# MainBoard.net
KiCad netlist of a schematic drawn in EAGLE
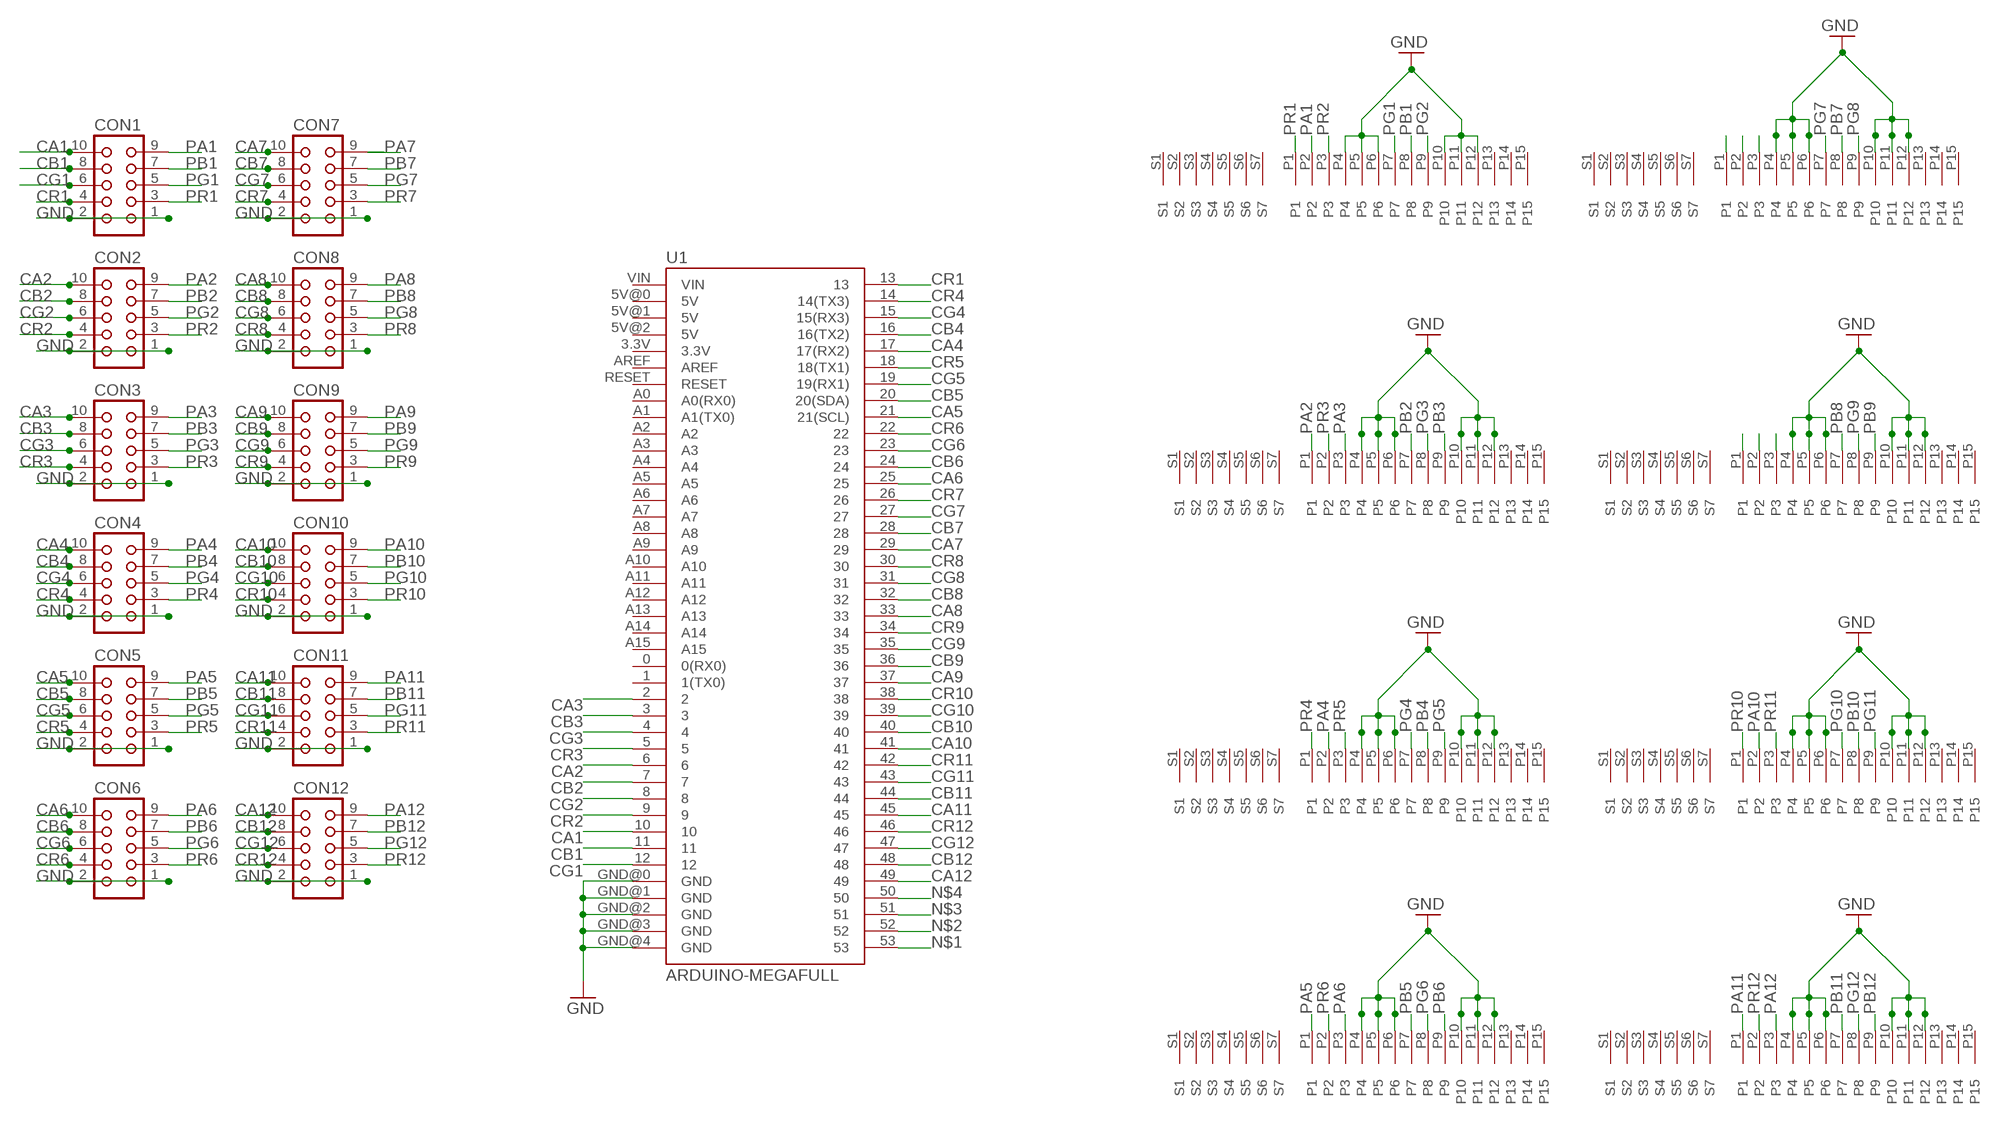
[diagram p0: schematic, sheet 1]

(export (version "E")
  (design (tool "Eeschema 10.0.6"))
  (components
    (comp (ref "CON1")
      (value "CON10")
      (footprint "eagle-import:CON10")
      (libsource (lib "eagle-import") (part "CON10"))
    )
    (comp (ref "CON2")
      (value "CON10")
      (footprint "eagle-import:CON10")
      (libsource (lib "eagle-import") (part "CON10"))
    )
    (comp (ref "CON3")
      (value "CON10")
      (footprint "eagle-import:CON10")
      (libsource (lib "eagle-import") (part "CON10"))
    )
    (comp (ref "CON4")
      (value "CON10")
      (footprint "eagle-import:CON10")
      (libsource (lib "eagle-import") (part "CON10"))
    )
    (comp (ref "CON5")
      (value "CON10")
      (footprint "eagle-import:CON10")
      (libsource (lib "eagle-import") (part "CON10"))
    )
    (comp (ref "CON6")
      (value "CON10")
      (footprint "eagle-import:CON10")
      (libsource (lib "eagle-import") (part "CON10"))
    )
    (comp (ref "CON7")
      (value "CON10")
      (footprint "eagle-import:CON10")
      (libsource (lib "eagle-import") (part "CON10"))
    )
    (comp (ref "CON8")
      (value "CON10")
      (footprint "eagle-import:CON10")
      (libsource (lib "eagle-import") (part "CON10"))
    )
    (comp (ref "CON9")
      (value "CON10")
      (footprint "eagle-import:CON10")
      (libsource (lib "eagle-import") (part "CON10"))
    )
    (comp (ref "CON10")
      (value "CON10")
      (footprint "eagle-import:CON10")
      (libsource (lib "eagle-import") (part "CON10"))
    )
    (comp (ref "CON11")
      (value "CON10")
      (footprint "eagle-import:CON10")
      (libsource (lib "eagle-import") (part "CON10"))
    )
    (comp (ref "CON12")
      (value "CON10")
      (footprint "eagle-import:CON10")
      (libsource (lib "eagle-import") (part "CON10"))
    )
    (comp (ref "P1")
      (value "87779-1001")
      (footprint "eagle-import:87779-1001")
      (libsource (lib "eagle-import") (part "87779-1001"))
    )
    (comp (ref "U$2")
      (value "87779-1001")
      (footprint "eagle-import:87779-1001")
      (libsource (lib "eagle-import") (part "87779-1001"))
    )
    (comp (ref "U$3")
      (value "87779-1001")
      (footprint "eagle-import:87779-1001")
      (libsource (lib "eagle-import") (part "87779-1001"))
    )
    (comp (ref "U$4")
      (value "87779-1001")
      (footprint "eagle-import:87779-1001")
      (libsource (lib "eagle-import") (part "87779-1001"))
    )
    (comp (ref "U$5")
      (value "87779-1001")
      (footprint "eagle-import:87779-1001")
      (libsource (lib "eagle-import") (part "87779-1001"))
    )
    (comp (ref "U$6")
      (value "87779-1001")
      (footprint "eagle-import:87779-1001")
      (libsource (lib "eagle-import") (part "87779-1001"))
    )
    (comp (ref "U$7")
      (value "87779-1001")
      (footprint "eagle-import:87779-1001")
      (libsource (lib "eagle-import") (part "87779-1001"))
    )
    (comp (ref "U$8")
      (value "87779-1001")
      (footprint "eagle-import:87779-1001")
      (libsource (lib "eagle-import") (part "87779-1001"))
    )
    (comp (ref "U1")
      (value "ARDUINO-MEGAFULL")
      (footprint "eagle-import:ARDUINO_MEGA")
      (libsource (lib "eagle-import") (part "ARDUINO-MEGAFULL"))
    )
  )
  (nets
    (net (code "1") (name "/CA1") (class "Default")
      (node (ref "CON1") (pin "10") (pinfunction "10_10") (pintype "passive"))
      (node (ref "U1") (pin "10") (pinfunction "10_10") (pintype "bidirectional"))
    )
    (net (code "2") (name "/CA2") (class "Default")
      (node (ref "CON2") (pin "10") (pinfunction "10_10") (pintype "passive"))
      (node (ref "U1") (pin "6") (pinfunction "6_6") (pintype "bidirectional"))
    )
    (net (code "3") (name "/CA3") (class "Default")
      (node (ref "CON3") (pin "10") (pinfunction "10_10") (pintype "passive"))
      (node (ref "U1") (pin "2") (pinfunction "2_2") (pintype "bidirectional"))
    )
    (net (code "4") (name "/CA4") (class "Default")
      (node (ref "CON4") (pin "10") (pinfunction "10_10") (pintype "passive"))
      (node (ref "U1") (pin "17") (pinfunction "17(RX2)_17") (pintype "bidirectional"))
    )
    (net (code "5") (name "/CA5") (class "Default")
      (node (ref "CON5") (pin "10") (pinfunction "10_10") (pintype "passive"))
      (node (ref "U1") (pin "21") (pinfunction "21(SCL)_21") (pintype "bidirectional"))
    )
    (net (code "6") (name "/CA6") (class "Default")
      (node (ref "CON6") (pin "10") (pinfunction "10_10") (pintype "passive"))
      (node (ref "U1") (pin "25") (pinfunction "25_25") (pintype "bidirectional"))
    )
    (net (code "7") (name "/CA7") (class "Default")
      (node (ref "CON7") (pin "10") (pinfunction "10_10") (pintype "passive"))
      (node (ref "U1") (pin "29") (pinfunction "29_29") (pintype "bidirectional"))
    )
    (net (code "8") (name "/CA8") (class "Default")
      (node (ref "CON8") (pin "10") (pinfunction "10_10") (pintype "passive"))
      (node (ref "U1") (pin "33") (pinfunction "33_33") (pintype "bidirectional"))
    )
    (net (code "9") (name "/CA9") (class "Default")
      (node (ref "CON9") (pin "10") (pinfunction "10_10") (pintype "passive"))
      (node (ref "U1") (pin "37") (pinfunction "37_37") (pintype "bidirectional"))
    )
    (net (code "10") (name "/CA10") (class "Default")
      (node (ref "CON10") (pin "10") (pinfunction "10_10") (pintype "passive"))
      (node (ref "U1") (pin "41") (pinfunction "41_41") (pintype "bidirectional"))
    )
    (net (code "11") (name "/CA11") (class "Default")
      (node (ref "CON11") (pin "10") (pinfunction "10_10") (pintype "passive"))
      (node (ref "U1") (pin "45") (pinfunction "45_45") (pintype "bidirectional"))
    )
    (net (code "12") (name "/CA12") (class "Default")
      (node (ref "CON12") (pin "10") (pinfunction "10_10") (pintype "passive"))
      (node (ref "U1") (pin "49") (pinfunction "49_49") (pintype "bidirectional"))
    )
    (net (code "13") (name "/CB1") (class "Default")
      (node (ref "CON1") (pin "8") (pinfunction "8_8") (pintype "passive"))
      (node (ref "U1") (pin "11") (pinfunction "11_11") (pintype "bidirectional"))
    )
    (net (code "14") (name "/CB2") (class "Default")
      (node (ref "CON2") (pin "8") (pinfunction "8_8") (pintype "passive"))
      (node (ref "U1") (pin "7") (pinfunction "7_7") (pintype "bidirectional"))
    )
    (net (code "15") (name "/CB3") (class "Default")
      (node (ref "CON3") (pin "8") (pinfunction "8_8") (pintype "passive"))
      (node (ref "U1") (pin "3") (pinfunction "3_3") (pintype "bidirectional"))
    )
    (net (code "16") (name "/CB4") (class "Default")
      (node (ref "CON4") (pin "8") (pinfunction "8_8") (pintype "passive"))
      (node (ref "U1") (pin "16") (pinfunction "16(TX2)_16") (pintype "bidirectional"))
    )
    (net (code "17") (name "/CB5") (class "Default")
      (node (ref "CON5") (pin "8") (pinfunction "8_8") (pintype "passive"))
      (node (ref "U1") (pin "20") (pinfunction "20(SDA)_20") (pintype "bidirectional"))
    )
    (net (code "18") (name "/CB6") (class "Default")
      (node (ref "CON6") (pin "8") (pinfunction "8_8") (pintype "passive"))
      (node (ref "U1") (pin "24") (pinfunction "24_24") (pintype "bidirectional"))
    )
    (net (code "19") (name "/CB7") (class "Default")
      (node (ref "CON7") (pin "8") (pinfunction "8_8") (pintype "passive"))
      (node (ref "U1") (pin "28") (pinfunction "28_28") (pintype "bidirectional"))
    )
    (net (code "20") (name "/CB8") (class "Default")
      (node (ref "CON8") (pin "8") (pinfunction "8_8") (pintype "passive"))
      (node (ref "U1") (pin "32") (pinfunction "32_32") (pintype "bidirectional"))
    )
    (net (code "21") (name "/CB9") (class "Default")
      (node (ref "CON9") (pin "8") (pinfunction "8_8") (pintype "passive"))
      (node (ref "U1") (pin "36") (pinfunction "36_36") (pintype "bidirectional"))
    )
    (net (code "22") (name "/CB10") (class "Default")
      (node (ref "CON10") (pin "8") (pinfunction "8_8") (pintype "passive"))
      (node (ref "U1") (pin "40") (pinfunction "40_40") (pintype "bidirectional"))
    )
    (net (code "23") (name "/CB11") (class "Default")
      (node (ref "CON11") (pin "8") (pinfunction "8_8") (pintype "passive"))
      (node (ref "U1") (pin "44") (pinfunction "44_44") (pintype "bidirectional"))
    )
    (net (code "24") (name "/CB12") (class "Default")
      (node (ref "CON12") (pin "8") (pinfunction "8_8") (pintype "passive"))
      (node (ref "U1") (pin "48") (pinfunction "48_48") (pintype "bidirectional"))
    )
    (net (code "25") (name "/CG1") (class "Default")
      (node (ref "CON1") (pin "6") (pinfunction "6_6") (pintype "passive"))
      (node (ref "U1") (pin "12") (pinfunction "12_12") (pintype "bidirectional"))
    )
    (net (code "26") (name "/CG2") (class "Default")
      (node (ref "CON2") (pin "6") (pinfunction "6_6") (pintype "passive"))
      (node (ref "U1") (pin "8") (pinfunction "8_8") (pintype "bidirectional"))
    )
    (net (code "27") (name "/CG3") (class "Default")
      (node (ref "CON3") (pin "6") (pinfunction "6_6") (pintype "passive"))
      (node (ref "U1") (pin "4") (pinfunction "4_4") (pintype "bidirectional"))
    )
    (net (code "28") (name "/CG4") (class "Default")
      (node (ref "CON4") (pin "6") (pinfunction "6_6") (pintype "passive"))
      (node (ref "U1") (pin "15") (pinfunction "15(RX3)_15") (pintype "bidirectional"))
    )
    (net (code "29") (name "/CG5") (class "Default")
      (node (ref "CON5") (pin "6") (pinfunction "6_6") (pintype "passive"))
      (node (ref "U1") (pin "19") (pinfunction "19(RX1)_19") (pintype "bidirectional"))
    )
    (net (code "30") (name "/CG6") (class "Default")
      (node (ref "CON6") (pin "6") (pinfunction "6_6") (pintype "passive"))
      (node (ref "U1") (pin "23") (pinfunction "23_23") (pintype "bidirectional"))
    )
    (net (code "31") (name "/CG7") (class "Default")
      (node (ref "CON7") (pin "6") (pinfunction "6_6") (pintype "passive"))
      (node (ref "U1") (pin "27") (pinfunction "27_27") (pintype "bidirectional"))
    )
    (net (code "32") (name "/CG8") (class "Default")
      (node (ref "CON8") (pin "6") (pinfunction "6_6") (pintype "passive"))
      (node (ref "U1") (pin "31") (pinfunction "31_31") (pintype "bidirectional"))
    )
    (net (code "33") (name "/CG9") (class "Default")
      (node (ref "CON9") (pin "6") (pinfunction "6_6") (pintype "passive"))
      (node (ref "U1") (pin "35") (pinfunction "35_35") (pintype "bidirectional"))
    )
    (net (code "34") (name "/CG10") (class "Default")
      (node (ref "CON10") (pin "6") (pinfunction "6_6") (pintype "passive"))
      (node (ref "U1") (pin "39") (pinfunction "39_39") (pintype "bidirectional"))
    )
    (net (code "35") (name "/CG11") (class "Default")
      (node (ref "CON11") (pin "6") (pinfunction "6_6") (pintype "passive"))
      (node (ref "U1") (pin "43") (pinfunction "43_43") (pintype "bidirectional"))
    )
    (net (code "36") (name "/CG12") (class "Default")
      (node (ref "CON12") (pin "6") (pinfunction "6_6") (pintype "passive"))
      (node (ref "U1") (pin "47") (pinfunction "47_47") (pintype "bidirectional"))
    )
    (net (code "37") (name "/CR1") (class "Default")
      (node (ref "CON1") (pin "4") (pinfunction "4_4") (pintype "passive"))
      (node (ref "U1") (pin "13") (pinfunction "13_13") (pintype "bidirectional"))
    )
    (net (code "38") (name "/CR2") (class "Default")
      (node (ref "CON2") (pin "4") (pinfunction "4_4") (pintype "passive"))
      (node (ref "U1") (pin "9") (pinfunction "9_9") (pintype "bidirectional"))
    )
    (net (code "39") (name "/CR3") (class "Default")
      (node (ref "CON3") (pin "4") (pinfunction "4_4") (pintype "passive"))
      (node (ref "U1") (pin "5") (pinfunction "5_5") (pintype "bidirectional"))
    )
    (net (code "40") (name "/CR4") (class "Default")
      (node (ref "CON4") (pin "4") (pinfunction "4_4") (pintype "passive"))
      (node (ref "U1") (pin "14") (pinfunction "14(TX3)_14") (pintype "bidirectional"))
    )
    (net (code "41") (name "/CR5") (class "Default")
      (node (ref "CON5") (pin "4") (pinfunction "4_4") (pintype "passive"))
      (node (ref "U1") (pin "18") (pinfunction "18(TX1)_18") (pintype "bidirectional"))
    )
    (net (code "42") (name "/CR6") (class "Default")
      (node (ref "CON6") (pin "4") (pinfunction "4_4") (pintype "passive"))
      (node (ref "U1") (pin "22") (pinfunction "22_22") (pintype "bidirectional"))
    )
    (net (code "43") (name "/CR7") (class "Default")
      (node (ref "CON7") (pin "4") (pinfunction "4_4") (pintype "passive"))
      (node (ref "U1") (pin "26") (pinfunction "26_26") (pintype "bidirectional"))
    )
    (net (code "44") (name "/CR8") (class "Default")
      (node (ref "CON8") (pin "4") (pinfunction "4_4") (pintype "passive"))
      (node (ref "U1") (pin "30") (pinfunction "30_30") (pintype "bidirectional"))
    )
    (net (code "45") (name "/CR9") (class "Default")
      (node (ref "CON9") (pin "4") (pinfunction "4_4") (pintype "passive"))
      (node (ref "U1") (pin "34") (pinfunction "34_34") (pintype "bidirectional"))
    )
    (net (code "46") (name "/CR10") (class "Default")
      (node (ref "CON10") (pin "4") (pinfunction "4_4") (pintype "passive"))
      (node (ref "U1") (pin "38") (pinfunction "38_38") (pintype "bidirectional"))
    )
    (net (code "47") (name "/CR11") (class "Default")
      (node (ref "CON11") (pin "4") (pinfunction "4_4") (pintype "passive"))
      (node (ref "U1") (pin "42") (pinfunction "42_42") (pintype "bidirectional"))
    )
    (net (code "48") (name "/CR12") (class "Default")
      (node (ref "CON12") (pin "4") (pinfunction "4_4") (pintype "passive"))
      (node (ref "U1") (pin "46") (pinfunction "46_46") (pintype "bidirectional"))
    )
    (net (code "49") (name "/N$1") (class "Default")
      (node (ref "U1") (pin "53") (pinfunction "53_53") (pintype "bidirectional"))
    )
    (net (code "50") (name "/N$2") (class "Default")
      (node (ref "U1") (pin "52") (pinfunction "52_52") (pintype "bidirectional"))
    )
    (net (code "51") (name "/N$3") (class "Default")
      (node (ref "U1") (pin "51") (pinfunction "51_51") (pintype "bidirectional"))
    )
    (net (code "52") (name "/N$4") (class "Default")
      (node (ref "U1") (pin "50") (pinfunction "50_50") (pintype "bidirectional"))
    )
    (net (code "53") (name "/PA1") (class "Default")
      (node (ref "CON1") (pin "9") (pinfunction "9_9") (pintype "passive"))
      (node (ref "P1") (pin "P2") (pinfunction "P2_P2") (pintype "bidirectional"))
    )
    (net (code "54") (name "/PA2") (class "Default")
      (node (ref "CON2") (pin "9") (pinfunction "9_9") (pintype "passive"))
      (node (ref "U$2") (pin "P1") (pinfunction "P1_P1") (pintype "bidirectional"))
    )
    (net (code "55") (name "/PA3") (class "Default")
      (node (ref "CON3") (pin "9") (pinfunction "9_9") (pintype "passive"))
      (node (ref "U$2") (pin "P3") (pinfunction "P3_P3") (pintype "bidirectional"))
    )
    (net (code "56") (name "/PA4") (class "Default")
      (node (ref "CON4") (pin "9") (pinfunction "9_9") (pintype "passive"))
      (node (ref "U$3") (pin "P2") (pinfunction "P2_P2") (pintype "bidirectional"))
    )
    (net (code "57") (name "/PA5") (class "Default")
      (node (ref "CON5") (pin "9") (pinfunction "9_9") (pintype "passive"))
      (node (ref "U$4") (pin "P1") (pinfunction "P1_P1") (pintype "bidirectional"))
    )
    (net (code "58") (name "/PA6") (class "Default")
      (node (ref "CON6") (pin "9") (pinfunction "9_9") (pintype "passive"))
      (node (ref "U$4") (pin "P3") (pinfunction "P3_P3") (pintype "bidirectional"))
    )
    (net (code "59") (name "/PA7") (class "Default")
      (node (ref "CON7") (pin "9") (pinfunction "9_9") (pintype "passive"))
      (node (ref "U$5") (pin "P2") (pinfunction "P2_P2") (pintype "bidirectional"))
    )
    (net (code "60") (name "/PA8") (class "Default")
      (node (ref "CON8") (pin "9") (pinfunction "9_9") (pintype "passive"))
      (node (ref "U$6") (pin "P1") (pinfunction "P1_P1") (pintype "bidirectional"))
    )
    (net (code "61") (name "/PA9") (class "Default")
      (node (ref "CON9") (pin "9") (pinfunction "9_9") (pintype "passive"))
      (node (ref "U$6") (pin "P3") (pinfunction "P3_P3") (pintype "bidirectional"))
    )
    (net (code "62") (name "/PA10") (class "Default")
      (node (ref "CON10") (pin "9") (pinfunction "9_9") (pintype "passive"))
      (node (ref "U$7") (pin "P2") (pinfunction "P2_P2") (pintype "bidirectional"))
    )
    (net (code "63") (name "/PA11") (class "Default")
      (node (ref "CON11") (pin "9") (pinfunction "9_9") (pintype "passive"))
      (node (ref "U$8") (pin "P1") (pinfunction "P1_P1") (pintype "bidirectional"))
    )
    (net (code "64") (name "/PA12") (class "Default")
      (node (ref "CON12") (pin "9") (pinfunction "9_9") (pintype "passive"))
      (node (ref "U$8") (pin "P3") (pinfunction "P3_P3") (pintype "bidirectional"))
    )
    (net (code "65") (name "/PB1") (class "Default")
      (node (ref "CON1") (pin "7") (pinfunction "7_7") (pintype "passive"))
      (node (ref "P1") (pin "P8") (pinfunction "P8_P8") (pintype "bidirectional"))
    )
    (net (code "66") (name "/PB2") (class "Default")
      (node (ref "CON2") (pin "7") (pinfunction "7_7") (pintype "passive"))
      (node (ref "U$2") (pin "P7") (pinfunction "P7_P7") (pintype "bidirectional"))
    )
    (net (code "67") (name "/PB3") (class "Default")
      (node (ref "CON3") (pin "7") (pinfunction "7_7") (pintype "passive"))
      (node (ref "U$2") (pin "P9") (pinfunction "P9_P9") (pintype "bidirectional"))
    )
    (net (code "68") (name "/PB4") (class "Default")
      (node (ref "CON4") (pin "7") (pinfunction "7_7") (pintype "passive"))
      (node (ref "U$3") (pin "P8") (pinfunction "P8_P8") (pintype "bidirectional"))
    )
    (net (code "69") (name "/PB5") (class "Default")
      (node (ref "CON5") (pin "7") (pinfunction "7_7") (pintype "passive"))
      (node (ref "U$4") (pin "P7") (pinfunction "P7_P7") (pintype "bidirectional"))
    )
    (net (code "70") (name "/PB6") (class "Default")
      (node (ref "CON6") (pin "7") (pinfunction "7_7") (pintype "passive"))
      (node (ref "U$4") (pin "P9") (pinfunction "P9_P9") (pintype "bidirectional"))
    )
    (net (code "71") (name "/PB7") (class "Default")
      (node (ref "CON7") (pin "7") (pinfunction "7_7") (pintype "passive"))
      (node (ref "U$5") (pin "P8") (pinfunction "P8_P8") (pintype "bidirectional"))
    )
    (net (code "72") (name "/PB8") (class "Default")
      (node (ref "CON8") (pin "7") (pinfunction "7_7") (pintype "passive"))
      (node (ref "U$6") (pin "P7") (pinfunction "P7_P7") (pintype "bidirectional"))
    )
    (net (code "73") (name "/PB9") (class "Default")
      (node (ref "CON9") (pin "7") (pinfunction "7_7") (pintype "passive"))
      (node (ref "U$6") (pin "P9") (pinfunction "P9_P9") (pintype "bidirectional"))
    )
    (net (code "74") (name "/PB10") (class "Default")
      (node (ref "CON10") (pin "7") (pinfunction "7_7") (pintype "passive"))
      (node (ref "U$7") (pin "P8") (pinfunction "P8_P8") (pintype "bidirectional"))
    )
    (net (code "75") (name "/PB11") (class "Default")
      (node (ref "CON11") (pin "7") (pinfunction "7_7") (pintype "passive"))
      (node (ref "U$8") (pin "P7") (pinfunction "P7_P7") (pintype "bidirectional"))
    )
    (net (code "76") (name "/PB12") (class "Default")
      (node (ref "CON12") (pin "7") (pinfunction "7_7") (pintype "passive"))
      (node (ref "U$8") (pin "P9") (pinfunction "P9_P9") (pintype "bidirectional"))
    )
    (net (code "77") (name "/PG1") (class "Default")
      (node (ref "CON1") (pin "5") (pinfunction "5_5") (pintype "passive"))
      (node (ref "P1") (pin "P7") (pinfunction "P7_P7") (pintype "bidirectional"))
    )
    (net (code "78") (name "/PG2") (class "Default")
      (node (ref "CON2") (pin "5") (pinfunction "5_5") (pintype "passive"))
      (node (ref "P1") (pin "P9") (pinfunction "P9_P9") (pintype "bidirectional"))
    )
    (net (code "79") (name "/PG3") (class "Default")
      (node (ref "CON3") (pin "5") (pinfunction "5_5") (pintype "passive"))
      (node (ref "U$2") (pin "P8") (pinfunction "P8_P8") (pintype "bidirectional"))
    )
    (net (code "80") (name "/PG4") (class "Default")
      (node (ref "CON4") (pin "5") (pinfunction "5_5") (pintype "passive"))
      (node (ref "U$3") (pin "P7") (pinfunction "P7_P7") (pintype "bidirectional"))
    )
    (net (code "81") (name "/PG5") (class "Default")
      (node (ref "CON5") (pin "5") (pinfunction "5_5") (pintype "passive"))
      (node (ref "U$3") (pin "P9") (pinfunction "P9_P9") (pintype "bidirectional"))
    )
    (net (code "82") (name "/PG6") (class "Default")
      (node (ref "CON6") (pin "5") (pinfunction "5_5") (pintype "passive"))
      (node (ref "U$4") (pin "P8") (pinfunction "P8_P8") (pintype "bidirectional"))
    )
    (net (code "83") (name "/PG7") (class "Default")
      (node (ref "CON7") (pin "5") (pinfunction "5_5") (pintype "passive"))
      (node (ref "U$5") (pin "P7") (pinfunction "P7_P7") (pintype "bidirectional"))
    )
    (net (code "84") (name "/PG8") (class "Default")
      (node (ref "CON8") (pin "5") (pinfunction "5_5") (pintype "passive"))
      (node (ref "U$5") (pin "P9") (pinfunction "P9_P9") (pintype "bidirectional"))
    )
    (net (code "85") (name "/PG9") (class "Default")
      (node (ref "CON9") (pin "5") (pinfunction "5_5") (pintype "passive"))
      (node (ref "U$6") (pin "P8") (pinfunction "P8_P8") (pintype "bidirectional"))
    )
    (net (code "86") (name "/PG10") (class "Default")
      (node (ref "CON10") (pin "5") (pinfunction "5_5") (pintype "passive"))
      (node (ref "U$7") (pin "P7") (pinfunction "P7_P7") (pintype "bidirectional"))
    )
    (net (code "87") (name "/PG11") (class "Default")
      (node (ref "CON11") (pin "5") (pinfunction "5_5") (pintype "passive"))
      (node (ref "U$7") (pin "P9") (pinfunction "P9_P9") (pintype "bidirectional"))
    )
    (net (code "88") (name "/PG12") (class "Default")
      (node (ref "CON12") (pin "5") (pinfunction "5_5") (pintype "passive"))
      (node (ref "U$8") (pin "P8") (pinfunction "P8_P8") (pintype "bidirectional"))
    )
    (net (code "89") (name "/PR1") (class "Default")
      (node (ref "CON1") (pin "3") (pinfunction "3_3") (pintype "passive"))
      (node (ref "P1") (pin "P1") (pinfunction "P1_P1") (pintype "bidirectional"))
    )
    (net (code "90") (name "/PR2") (class "Default")
      (node (ref "CON2") (pin "3") (pinfunction "3_3") (pintype "passive"))
      (node (ref "P1") (pin "P3") (pinfunction "P3_P3") (pintype "bidirectional"))
    )
    (net (code "91") (name "/PR3") (class "Default")
      (node (ref "CON3") (pin "3") (pinfunction "3_3") (pintype "passive"))
      (node (ref "U$2") (pin "P2") (pinfunction "P2_P2") (pintype "bidirectional"))
    )
    (net (code "92") (name "/PR4") (class "Default")
      (node (ref "CON4") (pin "3") (pinfunction "3_3") (pintype "passive"))
      (node (ref "U$3") (pin "P1") (pinfunction "P1_P1") (pintype "bidirectional"))
    )
    (net (code "93") (name "/PR5") (class "Default")
      (node (ref "CON5") (pin "3") (pinfunction "3_3") (pintype "passive"))
      (node (ref "U$3") (pin "P3") (pinfunction "P3_P3") (pintype "bidirectional"))
    )
    (net (code "94") (name "/PR6") (class "Default")
      (node (ref "CON6") (pin "3") (pinfunction "3_3") (pintype "passive"))
      (node (ref "U$4") (pin "P2") (pinfunction "P2_P2") (pintype "bidirectional"))
    )
    (net (code "95") (name "/PR7") (class "Default")
      (node (ref "CON7") (pin "3") (pinfunction "3_3") (pintype "passive"))
      (node (ref "U$5") (pin "P1") (pinfunction "P1_P1") (pintype "bidirectional"))
    )
    (net (code "96") (name "/PR8") (class "Default")
      (node (ref "CON8") (pin "3") (pinfunction "3_3") (pintype "passive"))
      (node (ref "U$5") (pin "P3") (pinfunction "P3_P3") (pintype "bidirectional"))
    )
    (net (code "97") (name "/PR9") (class "Default")
      (node (ref "CON9") (pin "3") (pinfunction "3_3") (pintype "passive"))
      (node (ref "U$6") (pin "P2") (pinfunction "P2_P2") (pintype "bidirectional"))
    )
    (net (code "98") (name "/PR10") (class "Default")
      (node (ref "CON10") (pin "3") (pinfunction "3_3") (pintype "passive"))
      (node (ref "U$7") (pin "P1") (pinfunction "P1_P1") (pintype "bidirectional"))
    )
    (net (code "99") (name "/PR11") (class "Default")
      (node (ref "CON11") (pin "3") (pinfunction "3_3") (pintype "passive"))
      (node (ref "U$7") (pin "P3") (pinfunction "P3_P3") (pintype "bidirectional"))
    )
    (net (code "100") (name "/PR12") (class "Default")
      (node (ref "CON12") (pin "3") (pinfunction "3_3") (pintype "passive"))
      (node (ref "U$8") (pin "P2") (pinfunction "P2_P2") (pintype "bidirectional"))
    )
    (net (code "101") (name "GND") (class "Default")
      (node (ref "CON1") (pin "1") (pinfunction "1_1") (pintype "passive"))
      (node (ref "CON1") (pin "2") (pinfunction "2_2") (pintype "passive"))
      (node (ref "CON10") (pin "1") (pinfunction "1_1") (pintype "passive"))
      (node (ref "CON10") (pin "2") (pinfunction "2_2") (pintype "passive"))
      (node (ref "CON11") (pin "1") (pinfunction "1_1") (pintype "passive"))
      (node (ref "CON11") (pin "2") (pinfunction "2_2") (pintype "passive"))
      (node (ref "CON12") (pin "1") (pinfunction "1_1") (pintype "passive"))
      (node (ref "CON12") (pin "2") (pinfunction "2_2") (pintype "passive"))
      (node (ref "CON2") (pin "1") (pinfunction "1_1") (pintype "passive"))
      (node (ref "CON2") (pin "2") (pinfunction "2_2") (pintype "passive"))
      (node (ref "CON3") (pin "1") (pinfunction "1_1") (pintype "passive"))
      (node (ref "CON3") (pin "2") (pinfunction "2_2") (pintype "passive"))
      (node (ref "CON4") (pin "1") (pinfunction "1_1") (pintype "passive"))
      (node (ref "CON4") (pin "2") (pinfunction "2_2") (pintype "passive"))
      (node (ref "CON5") (pin "1") (pinfunction "1_1") (pintype "passive"))
      (node (ref "CON5") (pin "2") (pinfunction "2_2") (pintype "passive"))
      (node (ref "CON6") (pin "1") (pinfunction "1_1") (pintype "passive"))
      (node (ref "CON6") (pin "2") (pinfunction "2_2") (pintype "passive"))
      (node (ref "CON7") (pin "1") (pinfunction "1_1") (pintype "passive"))
      (node (ref "CON7") (pin "2") (pinfunction "2_2") (pintype "passive"))
      (node (ref "CON8") (pin "1") (pinfunction "1_1") (pintype "passive"))
      (node (ref "CON8") (pin "2") (pinfunction "2_2") (pintype "passive"))
      (node (ref "CON9") (pin "1") (pinfunction "1_1") (pintype "passive"))
      (node (ref "CON9") (pin "2") (pinfunction "2_2") (pintype "passive"))
      (node (ref "P1") (pin "P10") (pinfunction "P10_P10") (pintype "bidirectional"))
      (node (ref "P1") (pin "P11") (pinfunction "P11_P11") (pintype "bidirectional"))
      (node (ref "P1") (pin "P12") (pinfunction "P12_P12") (pintype "bidirectional"))
      (node (ref "P1") (pin "P4") (pinfunction "P4_P4") (pintype "bidirectional"))
      (node (ref "P1") (pin "P5") (pinfunction "P5_P5") (pintype "bidirectional"))
      (node (ref "P1") (pin "P6") (pinfunction "P6_P6") (pintype "bidirectional"))
      (node (ref "U$2") (pin "P10") (pinfunction "P10_P10") (pintype "bidirectional"))
      (node (ref "U$2") (pin "P11") (pinfunction "P11_P11") (pintype "bidirectional"))
      (node (ref "U$2") (pin "P12") (pinfunction "P12_P12") (pintype "bidirectional"))
      (node (ref "U$2") (pin "P4") (pinfunction "P4_P4") (pintype "bidirectional"))
      (node (ref "U$2") (pin "P5") (pinfunction "P5_P5") (pintype "bidirectional"))
      (node (ref "U$2") (pin "P6") (pinfunction "P6_P6") (pintype "bidirectional"))
      (node (ref "U$3") (pin "P10") (pinfunction "P10_P10") (pintype "bidirectional"))
      (node (ref "U$3") (pin "P11") (pinfunction "P11_P11") (pintype "bidirectional"))
      (node (ref "U$3") (pin "P12") (pinfunction "P12_P12") (pintype "bidirectional"))
      (node (ref "U$3") (pin "P4") (pinfunction "P4_P4") (pintype "bidirectional"))
      (node (ref "U$3") (pin "P5") (pinfunction "P5_P5") (pintype "bidirectional"))
      (node (ref "U$3") (pin "P6") (pinfunction "P6_P6") (pintype "bidirectional"))
      (node (ref "U$4") (pin "P10") (pinfunction "P10_P10") (pintype "bidirectional"))
      (node (ref "U$4") (pin "P11") (pinfunction "P11_P11") (pintype "bidirectional"))
      (node (ref "U$4") (pin "P12") (pinfunction "P12_P12") (pintype "bidirectional"))
      (node (ref "U$4") (pin "P4") (pinfunction "P4_P4") (pintype "bidirectional"))
      (node (ref "U$4") (pin "P5") (pinfunction "P5_P5") (pintype "bidirectional"))
      (node (ref "U$4") (pin "P6") (pinfunction "P6_P6") (pintype "bidirectional"))
      (node (ref "U$5") (pin "P10") (pinfunction "P10_P10") (pintype "bidirectional"))
      (node (ref "U$5") (pin "P11") (pinfunction "P11_P11") (pintype "bidirectional"))
      (node (ref "U$5") (pin "P12") (pinfunction "P12_P12") (pintype "bidirectional"))
      (node (ref "U$5") (pin "P4") (pinfunction "P4_P4") (pintype "bidirectional"))
      (node (ref "U$5") (pin "P5") (pinfunction "P5_P5") (pintype "bidirectional"))
      (node (ref "U$5") (pin "P6") (pinfunction "P6_P6") (pintype "bidirectional"))
      (node (ref "U$6") (pin "P10") (pinfunction "P10_P10") (pintype "bidirectional"))
      (node (ref "U$6") (pin "P11") (pinfunction "P11_P11") (pintype "bidirectional"))
      (node (ref "U$6") (pin "P12") (pinfunction "P12_P12") (pintype "bidirectional"))
      (node (ref "U$6") (pin "P4") (pinfunction "P4_P4") (pintype "bidirectional"))
      (node (ref "U$6") (pin "P5") (pinfunction "P5_P5") (pintype "bidirectional"))
      (node (ref "U$6") (pin "P6") (pinfunction "P6_P6") (pintype "bidirectional"))
      (node (ref "U$7") (pin "P10") (pinfunction "P10_P10") (pintype "bidirectional"))
      (node (ref "U$7") (pin "P11") (pinfunction "P11_P11") (pintype "bidirectional"))
      (node (ref "U$7") (pin "P12") (pinfunction "P12_P12") (pintype "bidirectional"))
      (node (ref "U$7") (pin "P4") (pinfunction "P4_P4") (pintype "bidirectional"))
      (node (ref "U$7") (pin "P5") (pinfunction "P5_P5") (pintype "bidirectional"))
      (node (ref "U$7") (pin "P6") (pinfunction "P6_P6") (pintype "bidirectional"))
      (node (ref "U$8") (pin "P10") (pinfunction "P10_P10") (pintype "bidirectional"))
      (node (ref "U$8") (pin "P11") (pinfunction "P11_P11") (pintype "bidirectional"))
      (node (ref "U$8") (pin "P12") (pinfunction "P12_P12") (pintype "bidirectional"))
      (node (ref "U$8") (pin "P4") (pinfunction "P4_P4") (pintype "bidirectional"))
      (node (ref "U$8") (pin "P5") (pinfunction "P5_P5") (pintype "bidirectional"))
      (node (ref "U$8") (pin "P6") (pinfunction "P6_P6") (pintype "bidirectional"))
      (node (ref "U1") (pin "GND@0") (pinfunction "GND_GND@0") (pintype "bidirectional"))
      (node (ref "U1") (pin "GND@1") (pinfunction "GND_GND@1") (pintype "bidirectional"))
      (node (ref "U1") (pin "GND@2") (pinfunction "GND_GND@2") (pintype "bidirectional"))
      (node (ref "U1") (pin "GND@3") (pinfunction "GND_GND@3") (pintype "bidirectional"))
      (node (ref "U1") (pin "GND@4") (pinfunction "GND_GND@4") (pintype "bidirectional"))
    )
    (net (code "102") (name "unconnected-(P1-PadP13)") (class "Default")
      (node (ref "P1") (pin "P13") (pinfunction "P13_P13") (pintype "bidirectional"))
    )
    (net (code "103") (name "unconnected-(P1-PadP14)") (class "Default")
      (node (ref "P1") (pin "P14") (pinfunction "P14_P14") (pintype "bidirectional"))
    )
    (net (code "104") (name "unconnected-(P1-PadP15)") (class "Default")
      (node (ref "P1") (pin "P15") (pinfunction "P15_P15") (pintype "bidirectional"))
    )
    (net (code "105") (name "unconnected-(P1-PadS1)") (class "Default")
      (node (ref "P1") (pin "S1") (pinfunction "S1_S1") (pintype "bidirectional"))
    )
    (net (code "106") (name "unconnected-(P1-PadS2)") (class "Default")
      (node (ref "P1") (pin "S2") (pinfunction "S2_S2") (pintype "bidirectional"))
    )
    (net (code "107") (name "unconnected-(P1-PadS3)") (class "Default")
      (node (ref "P1") (pin "S3") (pinfunction "S3_S3") (pintype "bidirectional"))
    )
    (net (code "108") (name "unconnected-(P1-PadS4)") (class "Default")
      (node (ref "P1") (pin "S4") (pinfunction "S4_S4") (pintype "bidirectional"))
    )
    (net (code "109") (name "unconnected-(P1-PadS5)") (class "Default")
      (node (ref "P1") (pin "S5") (pinfunction "S5_S5") (pintype "bidirectional"))
    )
    (net (code "110") (name "unconnected-(P1-PadS6)") (class "Default")
      (node (ref "P1") (pin "S6") (pinfunction "S6_S6") (pintype "bidirectional"))
    )
    (net (code "111") (name "unconnected-(P1-PadS7)") (class "Default")
      (node (ref "P1") (pin "S7") (pinfunction "S7_S7") (pintype "bidirectional"))
    )
    (net (code "112") (name "unconnected-(U$2-PadP13)") (class "Default")
      (node (ref "U$2") (pin "P13") (pinfunction "P13_P13") (pintype "bidirectional"))
    )
    (net (code "113") (name "unconnected-(U$2-PadP14)") (class "Default")
      (node (ref "U$2") (pin "P14") (pinfunction "P14_P14") (pintype "bidirectional"))
    )
    (net (code "114") (name "unconnected-(U$2-PadP15)") (class "Default")
      (node (ref "U$2") (pin "P15") (pinfunction "P15_P15") (pintype "bidirectional"))
    )
    (net (code "115") (name "unconnected-(U$2-PadS1)") (class "Default")
      (node (ref "U$2") (pin "S1") (pinfunction "S1_S1") (pintype "bidirectional"))
    )
    (net (code "116") (name "unconnected-(U$2-PadS2)") (class "Default")
      (node (ref "U$2") (pin "S2") (pinfunction "S2_S2") (pintype "bidirectional"))
    )
    (net (code "117") (name "unconnected-(U$2-PadS3)") (class "Default")
      (node (ref "U$2") (pin "S3") (pinfunction "S3_S3") (pintype "bidirectional"))
    )
    (net (code "118") (name "unconnected-(U$2-PadS4)") (class "Default")
      (node (ref "U$2") (pin "S4") (pinfunction "S4_S4") (pintype "bidirectional"))
    )
    (net (code "119") (name "unconnected-(U$2-PadS5)") (class "Default")
      (node (ref "U$2") (pin "S5") (pinfunction "S5_S5") (pintype "bidirectional"))
    )
    (net (code "120") (name "unconnected-(U$2-PadS6)") (class "Default")
      (node (ref "U$2") (pin "S6") (pinfunction "S6_S6") (pintype "bidirectional"))
    )
    (net (code "121") (name "unconnected-(U$2-PadS7)") (class "Default")
      (node (ref "U$2") (pin "S7") (pinfunction "S7_S7") (pintype "bidirectional"))
    )
    (net (code "122") (name "unconnected-(U$3-PadP13)") (class "Default")
      (node (ref "U$3") (pin "P13") (pinfunction "P13_P13") (pintype "bidirectional"))
    )
    (net (code "123") (name "unconnected-(U$3-PadP14)") (class "Default")
      (node (ref "U$3") (pin "P14") (pinfunction "P14_P14") (pintype "bidirectional"))
    )
    (net (code "124") (name "unconnected-(U$3-PadP15)") (class "Default")
      (node (ref "U$3") (pin "P15") (pinfunction "P15_P15") (pintype "bidirectional"))
    )
    (net (code "125") (name "unconnected-(U$3-PadS1)") (class "Default")
      (node (ref "U$3") (pin "S1") (pinfunction "S1_S1") (pintype "bidirectional"))
    )
    (net (code "126") (name "unconnected-(U$3-PadS2)") (class "Default")
      (node (ref "U$3") (pin "S2") (pinfunction "S2_S2") (pintype "bidirectional"))
    )
    (net (code "127") (name "unconnected-(U$3-PadS3)") (class "Default")
      (node (ref "U$3") (pin "S3") (pinfunction "S3_S3") (pintype "bidirectional"))
    )
    (net (code "128") (name "unconnected-(U$3-PadS4)") (class "Default")
      (node (ref "U$3") (pin "S4") (pinfunction "S4_S4") (pintype "bidirectional"))
    )
    (net (code "129") (name "unconnected-(U$3-PadS5)") (class "Default")
      (node (ref "U$3") (pin "S5") (pinfunction "S5_S5") (pintype "bidirectional"))
    )
    (net (code "130") (name "unconnected-(U$3-PadS6)") (class "Default")
      (node (ref "U$3") (pin "S6") (pinfunction "S6_S6") (pintype "bidirectional"))
    )
    (net (code "131") (name "unconnected-(U$3-PadS7)") (class "Default")
      (node (ref "U$3") (pin "S7") (pinfunction "S7_S7") (pintype "bidirectional"))
    )
    (net (code "132") (name "unconnected-(U$4-PadP13)") (class "Default")
      (node (ref "U$4") (pin "P13") (pinfunction "P13_P13") (pintype "bidirectional"))
    )
    (net (code "133") (name "unconnected-(U$4-PadP14)") (class "Default")
      (node (ref "U$4") (pin "P14") (pinfunction "P14_P14") (pintype "bidirectional"))
    )
    (net (code "134") (name "unconnected-(U$4-PadP15)") (class "Default")
      (node (ref "U$4") (pin "P15") (pinfunction "P15_P15") (pintype "bidirectional"))
    )
    (net (code "135") (name "unconnected-(U$4-PadS1)") (class "Default")
      (node (ref "U$4") (pin "S1") (pinfunction "S1_S1") (pintype "bidirectional"))
    )
    (net (code "136") (name "unconnected-(U$4-PadS2)") (class "Default")
      (node (ref "U$4") (pin "S2") (pinfunction "S2_S2") (pintype "bidirectional"))
    )
    (net (code "137") (name "unconnected-(U$4-PadS3)") (class "Default")
      (node (ref "U$4") (pin "S3") (pinfunction "S3_S3") (pintype "bidirectional"))
    )
    (net (code "138") (name "unconnected-(U$4-PadS4)") (class "Default")
      (node (ref "U$4") (pin "S4") (pinfunction "S4_S4") (pintype "bidirectional"))
    )
    (net (code "139") (name "unconnected-(U$4-PadS5)") (class "Default")
      (node (ref "U$4") (pin "S5") (pinfunction "S5_S5") (pintype "bidirectional"))
    )
    (net (code "140") (name "unconnected-(U$4-PadS6)") (class "Default")
      (node (ref "U$4") (pin "S6") (pinfunction "S6_S6") (pintype "bidirectional"))
    )
    (net (code "141") (name "unconnected-(U$4-PadS7)") (class "Default")
      (node (ref "U$4") (pin "S7") (pinfunction "S7_S7") (pintype "bidirectional"))
    )
    (net (code "142") (name "unconnected-(U$5-PadP13)") (class "Default")
      (node (ref "U$5") (pin "P13") (pinfunction "P13_P13") (pintype "bidirectional"))
    )
    (net (code "143") (name "unconnected-(U$5-PadP14)") (class "Default")
      (node (ref "U$5") (pin "P14") (pinfunction "P14_P14") (pintype "bidirectional"))
    )
    (net (code "144") (name "unconnected-(U$5-PadP15)") (class "Default")
      (node (ref "U$5") (pin "P15") (pinfunction "P15_P15") (pintype "bidirectional"))
    )
    (net (code "145") (name "unconnected-(U$5-PadS1)") (class "Default")
      (node (ref "U$5") (pin "S1") (pinfunction "S1_S1") (pintype "bidirectional"))
    )
    (net (code "146") (name "unconnected-(U$5-PadS2)") (class "Default")
      (node (ref "U$5") (pin "S2") (pinfunction "S2_S2") (pintype "bidirectional"))
    )
    (net (code "147") (name "unconnected-(U$5-PadS3)") (class "Default")
      (node (ref "U$5") (pin "S3") (pinfunction "S3_S3") (pintype "bidirectional"))
    )
    (net (code "148") (name "unconnected-(U$5-PadS4)") (class "Default")
      (node (ref "U$5") (pin "S4") (pinfunction "S4_S4") (pintype "bidirectional"))
    )
    (net (code "149") (name "unconnected-(U$5-PadS5)") (class "Default")
      (node (ref "U$5") (pin "S5") (pinfunction "S5_S5") (pintype "bidirectional"))
    )
    (net (code "150") (name "unconnected-(U$5-PadS6)") (class "Default")
      (node (ref "U$5") (pin "S6") (pinfunction "S6_S6") (pintype "bidirectional"))
    )
    (net (code "151") (name "unconnected-(U$5-PadS7)") (class "Default")
      (node (ref "U$5") (pin "S7") (pinfunction "S7_S7") (pintype "bidirectional"))
    )
    (net (code "152") (name "unconnected-(U$6-PadP13)") (class "Default")
      (node (ref "U$6") (pin "P13") (pinfunction "P13_P13") (pintype "bidirectional"))
    )
    (net (code "153") (name "unconnected-(U$6-PadP14)") (class "Default")
      (node (ref "U$6") (pin "P14") (pinfunction "P14_P14") (pintype "bidirectional"))
    )
    (net (code "154") (name "unconnected-(U$6-PadP15)") (class "Default")
      (node (ref "U$6") (pin "P15") (pinfunction "P15_P15") (pintype "bidirectional"))
    )
    (net (code "155") (name "unconnected-(U$6-PadS1)") (class "Default")
      (node (ref "U$6") (pin "S1") (pinfunction "S1_S1") (pintype "bidirectional"))
    )
    (net (code "156") (name "unconnected-(U$6-PadS2)") (class "Default")
      (node (ref "U$6") (pin "S2") (pinfunction "S2_S2") (pintype "bidirectional"))
    )
    (net (code "157") (name "unconnected-(U$6-PadS3)") (class "Default")
      (node (ref "U$6") (pin "S3") (pinfunction "S3_S3") (pintype "bidirectional"))
    )
    (net (code "158") (name "unconnected-(U$6-PadS4)") (class "Default")
      (node (ref "U$6") (pin "S4") (pinfunction "S4_S4") (pintype "bidirectional"))
    )
    (net (code "159") (name "unconnected-(U$6-PadS5)") (class "Default")
      (node (ref "U$6") (pin "S5") (pinfunction "S5_S5") (pintype "bidirectional"))
    )
    (net (code "160") (name "unconnected-(U$6-PadS6)") (class "Default")
      (node (ref "U$6") (pin "S6") (pinfunction "S6_S6") (pintype "bidirectional"))
    )
    (net (code "161") (name "unconnected-(U$6-PadS7)") (class "Default")
      (node (ref "U$6") (pin "S7") (pinfunction "S7_S7") (pintype "bidirectional"))
    )
    (net (code "162") (name "unconnected-(U$7-PadP13)") (class "Default")
      (node (ref "U$7") (pin "P13") (pinfunction "P13_P13") (pintype "bidirectional"))
    )
    (net (code "163") (name "unconnected-(U$7-PadP14)") (class "Default")
      (node (ref "U$7") (pin "P14") (pinfunction "P14_P14") (pintype "bidirectional"))
    )
    (net (code "164") (name "unconnected-(U$7-PadP15)") (class "Default")
      (node (ref "U$7") (pin "P15") (pinfunction "P15_P15") (pintype "bidirectional"))
    )
    (net (code "165") (name "unconnected-(U$7-PadS1)") (class "Default")
      (node (ref "U$7") (pin "S1") (pinfunction "S1_S1") (pintype "bidirectional"))
    )
    (net (code "166") (name "unconnected-(U$7-PadS2)") (class "Default")
      (node (ref "U$7") (pin "S2") (pinfunction "S2_S2") (pintype "bidirectional"))
    )
    (net (code "167") (name "unconnected-(U$7-PadS3)") (class "Default")
      (node (ref "U$7") (pin "S3") (pinfunction "S3_S3") (pintype "bidirectional"))
    )
    (net (code "168") (name "unconnected-(U$7-PadS4)") (class "Default")
      (node (ref "U$7") (pin "S4") (pinfunction "S4_S4") (pintype "bidirectional"))
    )
    (net (code "169") (name "unconnected-(U$7-PadS5)") (class "Default")
      (node (ref "U$7") (pin "S5") (pinfunction "S5_S5") (pintype "bidirectional"))
    )
    (net (code "170") (name "unconnected-(U$7-PadS6)") (class "Default")
      (node (ref "U$7") (pin "S6") (pinfunction "S6_S6") (pintype "bidirectional"))
    )
    (net (code "171") (name "unconnected-(U$7-PadS7)") (class "Default")
      (node (ref "U$7") (pin "S7") (pinfunction "S7_S7") (pintype "bidirectional"))
    )
    (net (code "172") (name "unconnected-(U$8-PadP13)") (class "Default")
      (node (ref "U$8") (pin "P13") (pinfunction "P13_P13") (pintype "bidirectional"))
    )
    (net (code "173") (name "unconnected-(U$8-PadP14)") (class "Default")
      (node (ref "U$8") (pin "P14") (pinfunction "P14_P14") (pintype "bidirectional"))
    )
    (net (code "174") (name "unconnected-(U$8-PadP15)") (class "Default")
      (node (ref "U$8") (pin "P15") (pinfunction "P15_P15") (pintype "bidirectional"))
    )
    (net (code "175") (name "unconnected-(U$8-PadS1)") (class "Default")
      (node (ref "U$8") (pin "S1") (pinfunction "S1_S1") (pintype "bidirectional"))
    )
    (net (code "176") (name "unconnected-(U$8-PadS2)") (class "Default")
      (node (ref "U$8") (pin "S2") (pinfunction "S2_S2") (pintype "bidirectional"))
    )
    (net (code "177") (name "unconnected-(U$8-PadS3)") (class "Default")
      (node (ref "U$8") (pin "S3") (pinfunction "S3_S3") (pintype "bidirectional"))
    )
    (net (code "178") (name "unconnected-(U$8-PadS4)") (class "Default")
      (node (ref "U$8") (pin "S4") (pinfunction "S4_S4") (pintype "bidirectional"))
    )
    (net (code "179") (name "unconnected-(U$8-PadS5)") (class "Default")
      (node (ref "U$8") (pin "S5") (pinfunction "S5_S5") (pintype "bidirectional"))
    )
    (net (code "180") (name "unconnected-(U$8-PadS6)") (class "Default")
      (node (ref "U$8") (pin "S6") (pinfunction "S6_S6") (pintype "bidirectional"))
    )
    (net (code "181") (name "unconnected-(U$8-PadS7)") (class "Default")
      (node (ref "U$8") (pin "S7") (pinfunction "S7_S7") (pintype "bidirectional"))
    )
    (net (code "182") (name "unconnected-(U1-0(RX0)-Pad0)") (class "Default")
      (node (ref "U1") (pin "0") (pinfunction "0(RX0)_0") (pintype "bidirectional"))
    )
    (net (code "183") (name "unconnected-(U1-1(TX0)-Pad1)") (class "Default")
      (node (ref "U1") (pin "1") (pinfunction "1(TX0)_1") (pintype "bidirectional"))
    )
    (net (code "184") (name "unconnected-(U1-5V-Pad5V@0)") (class "Default")
      (node (ref "U1") (pin "5V@0") (pinfunction "5V_5V@0") (pintype "bidirectional"))
    )
    (net (code "185") (name "unconnected-(U1-5V-Pad5V@1)") (class "Default")
      (node (ref "U1") (pin "5V@1") (pinfunction "5V_5V@1") (pintype "bidirectional"))
    )
    (net (code "186") (name "unconnected-(U1-5V-Pad5V@2)") (class "Default")
      (node (ref "U1") (pin "5V@2") (pinfunction "5V_5V@2") (pintype "bidirectional"))
    )
    (net (code "187") (name "unconnected-(U1-A0(RX0)-PadA0)") (class "Default")
      (node (ref "U1") (pin "A0") (pinfunction "A0(RX0)_A0") (pintype "bidirectional"))
    )
    (net (code "188") (name "unconnected-(U1-A1(TX0)-PadA1)") (class "Default")
      (node (ref "U1") (pin "A1") (pinfunction "A1(TX0)_A1") (pintype "bidirectional"))
    )
    (net (code "189") (name "unconnected-(U1-Pad3.3V)") (class "Default")
      (node (ref "U1") (pin "3.3V") (pinfunction "3.3V_3.3V") (pintype "bidirectional"))
    )
    (net (code "190") (name "unconnected-(U1-PadA2)") (class "Default")
      (node (ref "U1") (pin "A2") (pinfunction "A2_A2") (pintype "bidirectional"))
    )
    (net (code "191") (name "unconnected-(U1-PadA3)") (class "Default")
      (node (ref "U1") (pin "A3") (pinfunction "A3_A3") (pintype "bidirectional"))
    )
    (net (code "192") (name "unconnected-(U1-PadA4)") (class "Default")
      (node (ref "U1") (pin "A4") (pinfunction "A4_A4") (pintype "bidirectional"))
    )
    (net (code "193") (name "unconnected-(U1-PadA5)") (class "Default")
      (node (ref "U1") (pin "A5") (pinfunction "A5_A5") (pintype "bidirectional"))
    )
    (net (code "194") (name "unconnected-(U1-PadA6)") (class "Default")
      (node (ref "U1") (pin "A6") (pinfunction "A6_A6") (pintype "bidirectional"))
    )
    (net (code "195") (name "unconnected-(U1-PadA7)") (class "Default")
      (node (ref "U1") (pin "A7") (pinfunction "A7_A7") (pintype "bidirectional"))
    )
    (net (code "196") (name "unconnected-(U1-PadA8)") (class "Default")
      (node (ref "U1") (pin "A8") (pinfunction "A8_A8") (pintype "bidirectional"))
    )
    (net (code "197") (name "unconnected-(U1-PadA9)") (class "Default")
      (node (ref "U1") (pin "A9") (pinfunction "A9_A9") (pintype "bidirectional"))
    )
    (net (code "198") (name "unconnected-(U1-PadA10)") (class "Default")
      (node (ref "U1") (pin "A10") (pinfunction "A10_A10") (pintype "bidirectional"))
    )
    (net (code "199") (name "unconnected-(U1-PadA11)") (class "Default")
      (node (ref "U1") (pin "A11") (pinfunction "A11_A11") (pintype "bidirectional"))
    )
    (net (code "200") (name "unconnected-(U1-PadA12)") (class "Default")
      (node (ref "U1") (pin "A12") (pinfunction "A12_A12") (pintype "bidirectional"))
    )
    (net (code "201") (name "unconnected-(U1-PadA13)") (class "Default")
      (node (ref "U1") (pin "A13") (pinfunction "A13_A13") (pintype "bidirectional"))
    )
    (net (code "202") (name "unconnected-(U1-PadA14)") (class "Default")
      (node (ref "U1") (pin "A14") (pinfunction "A14_A14") (pintype "bidirectional"))
    )
    (net (code "203") (name "unconnected-(U1-PadA15)") (class "Default")
      (node (ref "U1") (pin "A15") (pinfunction "A15_A15") (pintype "bidirectional"))
    )
    (net (code "204") (name "unconnected-(U1-PadAREF)") (class "Default")
      (node (ref "U1") (pin "AREF") (pinfunction "AREF_AREF") (pintype "bidirectional"))
    )
    (net (code "205") (name "unconnected-(U1-PadRESET)") (class "Default")
      (node (ref "U1") (pin "RESET") (pinfunction "RESET_RESET") (pintype "bidirectional"))
    )
    (net (code "206") (name "unconnected-(U1-PadVIN)") (class "Default")
      (node (ref "U1") (pin "VIN") (pinfunction "VIN_VIN") (pintype "bidirectional"))
    )
  )
)
